# Transceivers.net
KiCad netlist of a schematic drawn in Altium Designer
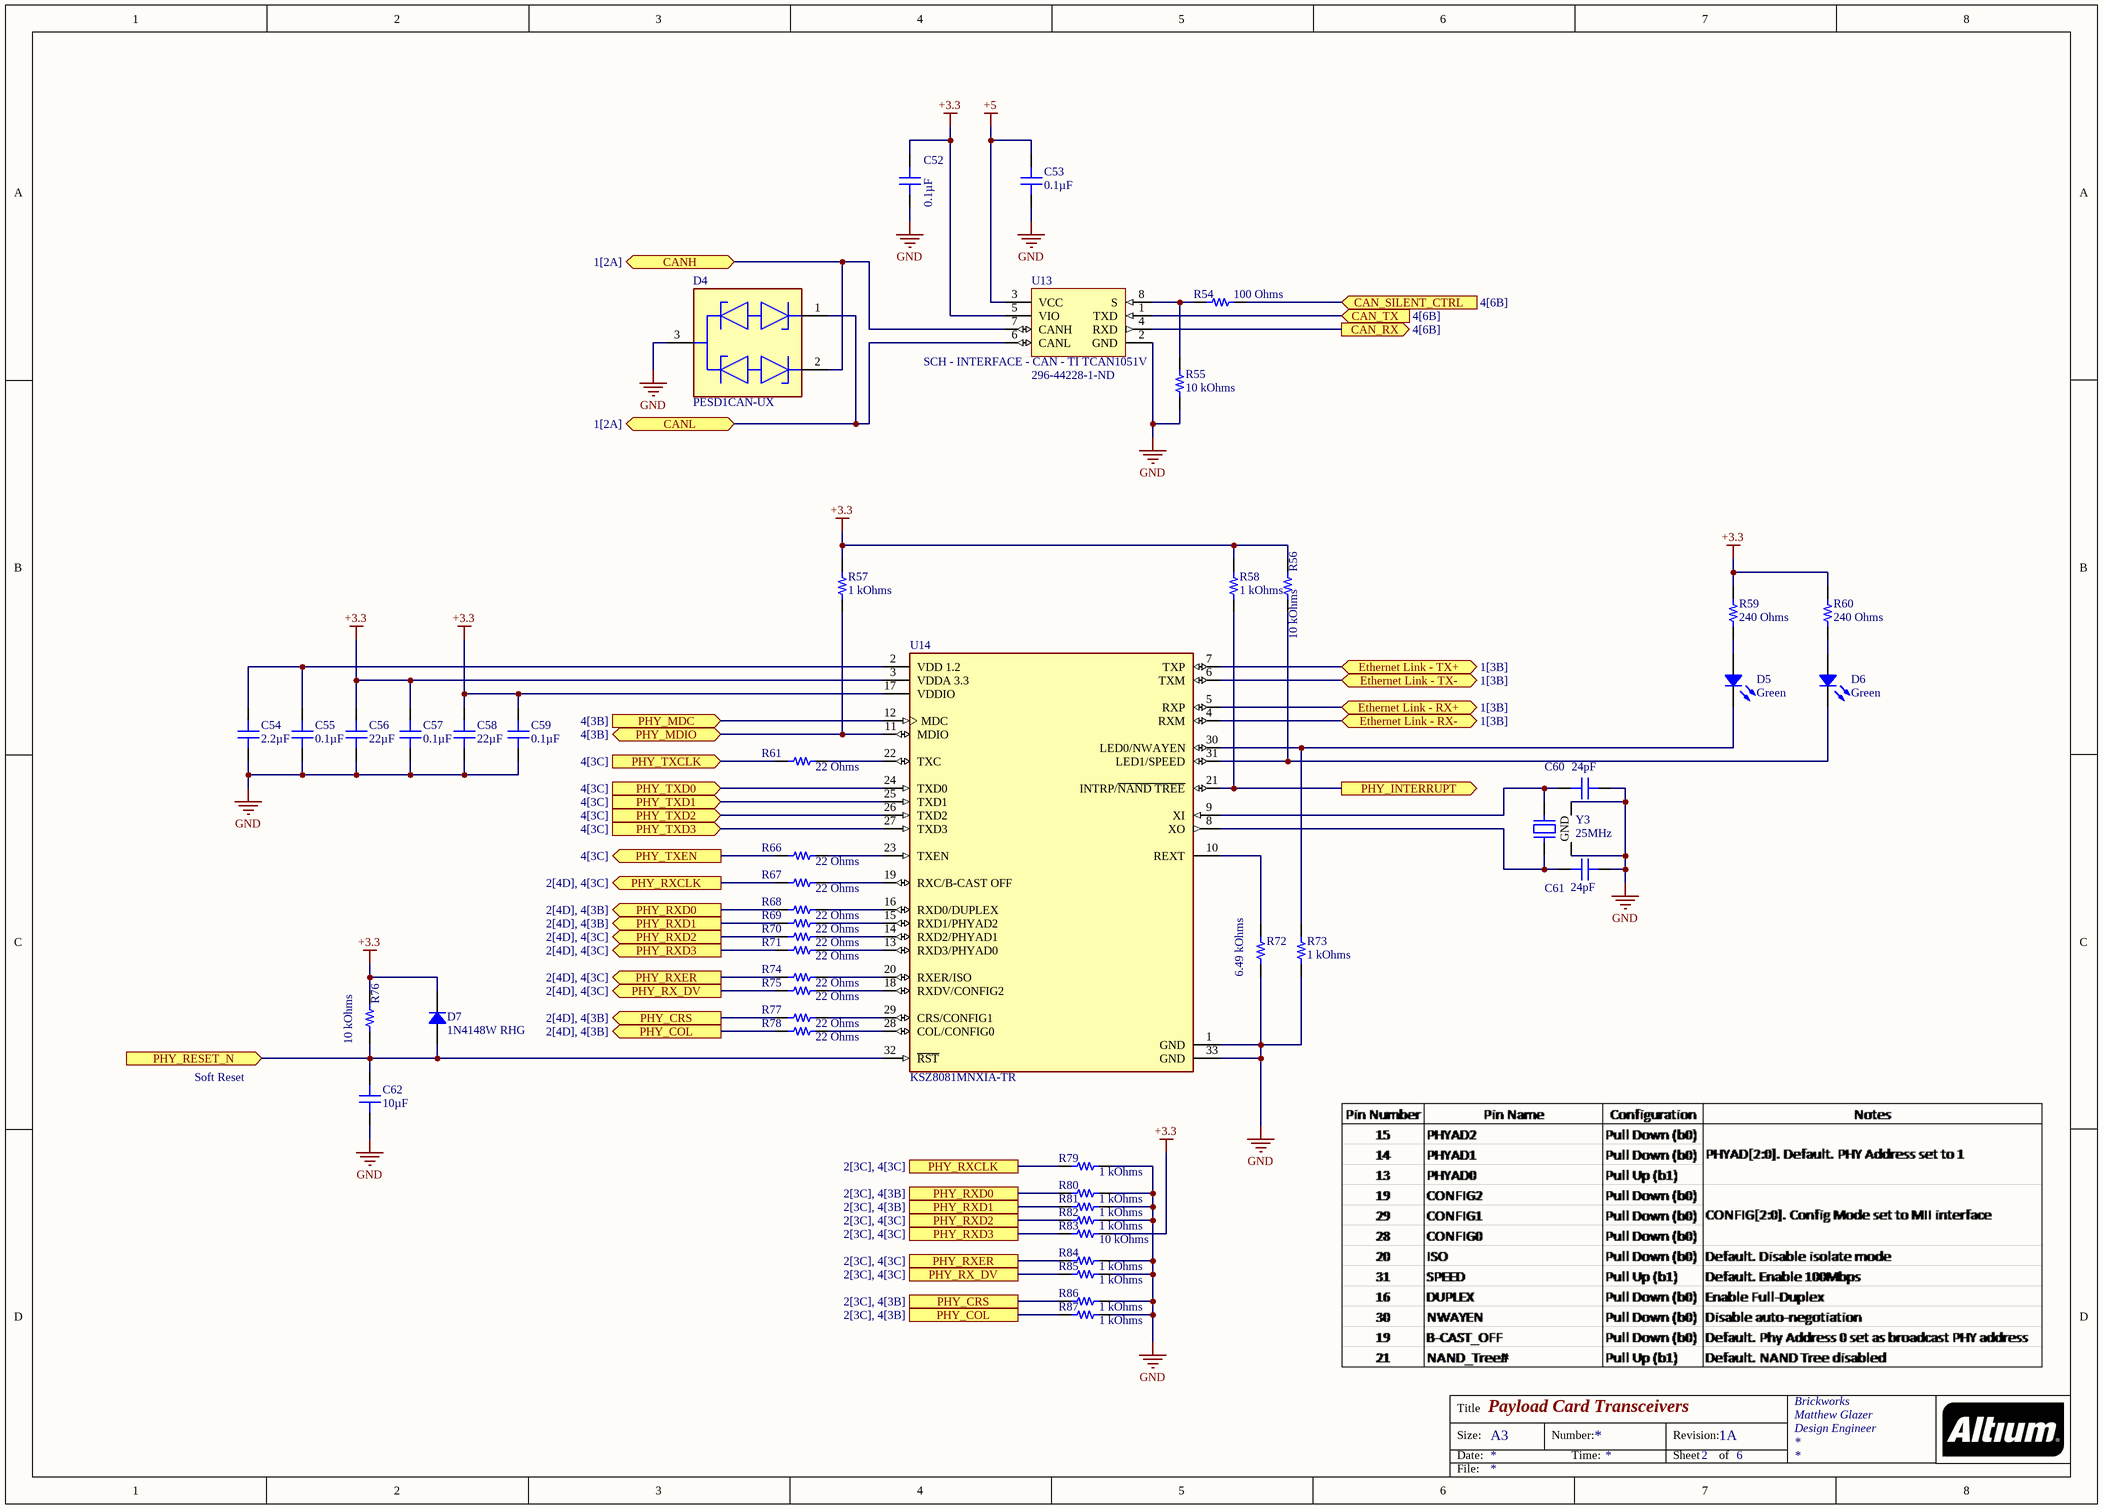
[diagram p0: Transceivers.SchDoc]

(export (version "E")
  (design (tool "Eeschema 10.0.6"))
  (components
    (comp (ref "C52")
      (value "0.1µF")
      (footprint "CAP 0603_1608")
      (description "CAP CER 0.1UF 25V X7R 0603")
      (fields
        (field (name "PART NUMBER") "CL10B104KA8WPNC")
        (field (name "MANUFACTURER") "Samsung Electro-Mechanics")
      )
      (libsource (lib "Celestial Altium Library - altium_library") (part "Capacitor"))
    )
    (comp (ref "C53")
      (value "0.1µF")
      (footprint "CAP 0603_1608")
      (description "CAP CER 0.1UF 25V X7R 0603")
      (fields
        (field (name "PART NUMBER") "CL10B104KA8WPNC")
        (field (name "MANUFACTURER") "Samsung Electro-Mechanics")
      )
      (libsource (lib "Celestial Altium Library - altium_library") (part "Capacitor"))
    )
    (comp (ref "C54")
      (value "2.2µF")
      (footprint "CAP 0805_2012")
      (description "CAP CER 2.2UF 10V X5R 0805")
      (fields
        (field (name "PART NUMBER") "CL21A225KPFNNNE")
        (field (name "MANUFACTURER") "Samsung Electro-Mechanics")
      )
      (libsource (lib "Celestial Altium Library - altium_library") (part "Capacitor"))
    )
    (comp (ref "C55")
      (value "0.1µF")
      (footprint "CAP 0603_1608")
      (description "CAP CER 0.1UF 25V X7R 0603")
      (fields
        (field (name "PART NUMBER") "CL10B104KA8WPNC")
        (field (name "MANUFACTURER") "Samsung Electro-Mechanics")
      )
      (libsource (lib "Celestial Altium Library - altium_library") (part "Capacitor"))
    )
    (comp (ref "C56")
      (value "22µF")
      (footprint "CAP 0805_2012")
      (description "CAP CER 22UF 10V X5R 0805")
      (fields
        (field (name "PART NUMBER") "CL21A226KPCLRNC")
        (field (name "MANUFACTURER") "Samsung Electro-Mechanics")
      )
      (libsource (lib "Celestial Altium Library - altium_library") (part "Capacitor"))
    )
    (comp (ref "C57")
      (value "0.1µF")
      (footprint "CAP 0603_1608")
      (description "CAP CER 0.1UF 25V X7R 0603")
      (fields
        (field (name "PART NUMBER") "CL10B104KA8WPNC")
        (field (name "MANUFACTURER") "Samsung Electro-Mechanics")
      )
      (libsource (lib "Celestial Altium Library - altium_library") (part "Capacitor"))
    )
    (comp (ref "C58")
      (value "22µF")
      (footprint "CAP 0805_2012")
      (description "CAP CER 22UF 10V X5R 0805")
      (fields
        (field (name "PART NUMBER") "CL21A226KPCLRNC")
        (field (name "MANUFACTURER") "Samsung Electro-Mechanics")
      )
      (libsource (lib "Celestial Altium Library - altium_library") (part "Capacitor"))
    )
    (comp (ref "C59")
      (value "0.1µF")
      (footprint "CAP 0603_1608")
      (description "CAP CER 0.1UF 25V X7R 0603")
      (fields
        (field (name "PART NUMBER") "CL10B104KA8WPNC")
        (field (name "MANUFACTURER") "Samsung Electro-Mechanics")
      )
      (libsource (lib "Celestial Altium Library - altium_library") (part "Capacitor"))
    )
    (comp (ref "C60")
      (value "24pF")
      (footprint "CAP 0603_1608")
      (description "CAP CER 24PF 50V C0G/NP0 0603")
      (fields
        (field (name "PART NUMBER") "CL10C240JB8NNNC")
        (field (name "MANUFACTURER") "Samsung Electro-Mechanics")
      )
      (libsource (lib "Celestial Altium Library - altium_library") (part "Capacitor"))
    )
    (comp (ref "C61")
      (value "24pF")
      (footprint "CAP 0603_1608")
      (description "CAP CER 24PF 50V C0G/NP0 0603")
      (fields
        (field (name "PART NUMBER") "CL10C240JB8NNNC")
        (field (name "MANUFACTURER") "Samsung Electro-Mechanics")
      )
      (libsource (lib "Celestial Altium Library - altium_library") (part "Capacitor"))
    )
    (comp (ref "C62")
      (value "10µF")
      (footprint "CAP 0805_2012")
      (description "CAP CER 10UF 16V X5R 0805")
      (fields (field (name "PART NUMBER") "CC0805KKX5R7BB106") (field (name "MANUFACTURER") "Yageo"))
      (libsource (lib "Celestial Altium Library - altium_library") (part "Capacitor"))
    )
    (comp (ref "D4")
      (value "PESD1CAN-UX")
      (footprint "FP-SOT323-MFG")
      (description "TVS DIODE 24V 50V SC70-3")
      (libsource (lib "Altium Content Vault") (part "04d57993b6b7b0f5b3c95ba4f97dea0"))
    )
    (comp (ref "D5")
      (value "Green")
      (footprint "LED 0603_1608 GREEN")
      (description "LED GREEN CLEAR CHIP SMD")
      (fields (field (name "PART NUMBER") "LTST-C193KGKT-5A") (field (name "MANUFACTURER") "Lite-On Inc."))
      (libsource (lib "Celestial Altium Library - altium_library") (part "LED"))
    )
    (comp (ref "D6")
      (value "Green")
      (footprint "LED 0603_1608 GREEN")
      (description "LED GREEN CLEAR CHIP SMD")
      (fields (field (name "PART NUMBER") "LTST-C193KGKT-5A") (field (name "MANUFACTURER") "Lite-On Inc."))
      (libsource (lib "Celestial Altium Library - altium_library") (part "LED"))
    )
    (comp (ref "D7")
      (value "1N4148W RHG")
      (footprint "SOD123F")
      (description "DIODE GEN PURP 100V 150MA SOD123")
      (fields (field (name "MANUFACTURER") "Taiwan Semiconductor Corporation"))
      (libsource (lib "Celestial Altium Library - altium_library") (part "Diode"))
    )
    (comp (ref "R54")
      (value "100 Ohms")
      (footprint "RES 0603_1608")
      (description "RES 100 OHM 1% 1/10W 0603")
      (fields
        (field (name "PART NUMBER") "RMCF0603FG100R")
        (field (name "MANUFACTURER") "Stackpole Electronics Inc")
      )
      (libsource (lib "Celestial Altium Library - altium_library") (part "Resistor"))
    )
    (comp (ref "R55")
      (value "10 kOhms")
      (footprint "RES 0603_1608")
      (description "RES 10K OHM 5% 1/10W 0603")
      (fields
        (field (name "PART NUMBER") "RMCF0603JT10K0")
        (field (name "MANUFACTURER") "Stackpole Electronics Inc")
      )
      (libsource (lib "Celestial Altium Library - altium_library") (part "Resistor"))
    )
    (comp (ref "R56")
      (value "10 kOhms")
      (footprint "RES 0603_1608")
      (description "RES 10K OHM 5% 1/10W 0603")
      (fields
        (field (name "PART NUMBER") "RMCF0603JT10K0")
        (field (name "MANUFACTURER") "Stackpole Electronics Inc")
      )
      (libsource (lib "Celestial Altium Library - altium_library") (part "Resistor"))
    )
    (comp (ref "R57")
      (value "1 kOhms")
      (footprint "RES 0603_1608")
      (description "RES 1K OHM 1% 1/8W 0603")
      (fields
        (field (name "PART NUMBER") "RNCP0603FTD1K00")
        (field (name "MANUFACTURER") "Stackpole Electronics Inc")
      )
      (libsource (lib "Celestial Altium Library - altium_library") (part "Resistor"))
    )
    (comp (ref "R58")
      (value "1 kOhms")
      (footprint "RES 0603_1608")
      (description "RES 1K OHM 1% 1/8W 0603")
      (fields
        (field (name "PART NUMBER") "RNCP0603FTD1K00")
        (field (name "MANUFACTURER") "Stackpole Electronics Inc")
      )
      (libsource (lib "Celestial Altium Library - altium_library") (part "Resistor"))
    )
    (comp (ref "R59")
      (value "240 Ohms")
      (footprint "RES 0603_1608")
      (description "RES 240 OHM 5% 1/10W 0603")
      (fields
        (field (name "PART NUMBER") "RMCF0603JT240R")
        (field (name "MANUFACTURER") "Stackpole Electronics Inc")
      )
      (libsource (lib "Celestial Altium Library - altium_library") (part "Resistor"))
    )
    (comp (ref "R60")
      (value "240 Ohms")
      (footprint "RES 0603_1608")
      (description "RES 240 OHM 5% 1/10W 0603")
      (fields
        (field (name "PART NUMBER") "RMCF0603JT240R")
        (field (name "MANUFACTURER") "Stackpole Electronics Inc")
      )
      (libsource (lib "Celestial Altium Library - altium_library") (part "Resistor"))
    )
    (comp (ref "R61")
      (value "22 Ohms")
      (footprint "RES 0603_1608")
      (description "RES 22 OHM 1% 1/10W 0603")
      (fields
        (field (name "PART NUMBER") "RMCF0603FT22R0")
        (field (name "MANUFACTURER") "Stackpole Electronics Inc")
      )
      (libsource (lib "Celestial Altium Library - altium_library") (part "Resistor"))
    )
    (comp (ref "R66")
      (value "22 Ohms")
      (footprint "RES 0603_1608")
      (description "RES 22 OHM 1% 1/10W 0603")
      (fields
        (field (name "PART NUMBER") "RMCF0603FT22R0")
        (field (name "MANUFACTURER") "Stackpole Electronics Inc")
      )
      (libsource (lib "Celestial Altium Library - altium_library") (part "Resistor"))
    )
    (comp (ref "R67")
      (value "22 Ohms")
      (footprint "RES 0603_1608")
      (description "RES 22 OHM 1% 1/10W 0603")
      (fields
        (field (name "PART NUMBER") "RMCF0603FT22R0")
        (field (name "MANUFACTURER") "Stackpole Electronics Inc")
      )
      (libsource (lib "Celestial Altium Library - altium_library") (part "Resistor"))
    )
    (comp (ref "R68")
      (value "22 Ohms")
      (footprint "RES 0603_1608")
      (description "RES 22 OHM 1% 1/10W 0603")
      (fields
        (field (name "PART NUMBER") "RMCF0603FT22R0")
        (field (name "MANUFACTURER") "Stackpole Electronics Inc")
      )
      (libsource (lib "Celestial Altium Library - altium_library") (part "Resistor"))
    )
    (comp (ref "R69")
      (value "22 Ohms")
      (footprint "RES 0603_1608")
      (description "RES 22 OHM 1% 1/10W 0603")
      (fields
        (field (name "PART NUMBER") "RMCF0603FT22R0")
        (field (name "MANUFACTURER") "Stackpole Electronics Inc")
      )
      (libsource (lib "Celestial Altium Library - altium_library") (part "Resistor"))
    )
    (comp (ref "R70")
      (value "22 Ohms")
      (footprint "RES 0603_1608")
      (description "RES 22 OHM 1% 1/10W 0603")
      (fields
        (field (name "PART NUMBER") "RMCF0603FT22R0")
        (field (name "MANUFACTURER") "Stackpole Electronics Inc")
      )
      (libsource (lib "Celestial Altium Library - altium_library") (part "Resistor"))
    )
    (comp (ref "R71")
      (value "22 Ohms")
      (footprint "RES 0603_1608")
      (description "RES 22 OHM 1% 1/10W 0603")
      (fields
        (field (name "PART NUMBER") "RMCF0603FT22R0")
        (field (name "MANUFACTURER") "Stackpole Electronics Inc")
      )
      (libsource (lib "Celestial Altium Library - altium_library") (part "Resistor"))
    )
    (comp (ref "R72")
      (value "6.49 kOhms")
      (footprint "RES 0603_1608")
      (description "RES 6.49K OHM 1% 1/8W 0603")
      (fields
        (field (name "PART NUMBER") "RNCP0603FTD6K49")
        (field (name "MANUFACTURER") "Stackpole Electronics Inc")
      )
      (libsource (lib "Celestial Altium Library - altium_library") (part "Resistor"))
    )
    (comp (ref "R73")
      (value "1 kOhms")
      (footprint "RES 0603_1608")
      (description "RES 1K OHM 1% 1/8W 0603")
      (fields
        (field (name "PART NUMBER") "RNCP0603FTD1K00")
        (field (name "MANUFACTURER") "Stackpole Electronics Inc")
      )
      (libsource (lib "Celestial Altium Library - altium_library") (part "Resistor"))
    )
    (comp (ref "R74")
      (value "22 Ohms")
      (footprint "RES 0603_1608")
      (description "RES 22 OHM 1% 1/10W 0603")
      (fields
        (field (name "PART NUMBER") "RMCF0603FT22R0")
        (field (name "MANUFACTURER") "Stackpole Electronics Inc")
      )
      (libsource (lib "Celestial Altium Library - altium_library") (part "Resistor"))
    )
    (comp (ref "R75")
      (value "22 Ohms")
      (footprint "RES 0603_1608")
      (description "RES 22 OHM 1% 1/10W 0603")
      (fields
        (field (name "PART NUMBER") "RMCF0603FT22R0")
        (field (name "MANUFACTURER") "Stackpole Electronics Inc")
      )
      (libsource (lib "Celestial Altium Library - altium_library") (part "Resistor"))
    )
    (comp (ref "R76")
      (value "10 kOhms")
      (footprint "RES 0603_1608")
      (description "RES 10K OHM 5% 1/10W 0603")
      (fields
        (field (name "PART NUMBER") "RMCF0603JT10K0")
        (field (name "MANUFACTURER") "Stackpole Electronics Inc")
      )
      (libsource (lib "Celestial Altium Library - altium_library") (part "Resistor"))
    )
    (comp (ref "R77")
      (value "22 Ohms")
      (footprint "RES 0603_1608")
      (description "RES 22 OHM 1% 1/10W 0603")
      (fields
        (field (name "PART NUMBER") "RMCF0603FT22R0")
        (field (name "MANUFACTURER") "Stackpole Electronics Inc")
      )
      (libsource (lib "Celestial Altium Library - altium_library") (part "Resistor"))
    )
    (comp (ref "R78")
      (value "22 Ohms")
      (footprint "RES 0603_1608")
      (description "RES 22 OHM 1% 1/10W 0603")
      (fields
        (field (name "PART NUMBER") "RMCF0603FT22R0")
        (field (name "MANUFACTURER") "Stackpole Electronics Inc")
      )
      (libsource (lib "Celestial Altium Library - altium_library") (part "Resistor"))
    )
    (comp (ref "R79")
      (value "1 kOhms")
      (footprint "RES 0603_1608")
      (description "RES 1K OHM 1% 1/8W 0603")
      (fields
        (field (name "PART NUMBER") "RNCP0603FTD1K00")
        (field (name "MANUFACTURER") "Stackpole Electronics Inc")
      )
      (libsource (lib "Celestial Altium Library - altium_library") (part "Resistor"))
    )
    (comp (ref "R80")
      (value "1 kOhms")
      (footprint "RES 0603_1608")
      (description "RES 1K OHM 1% 1/8W 0603")
      (fields
        (field (name "PART NUMBER") "RNCP0603FTD1K00")
        (field (name "MANUFACTURER") "Stackpole Electronics Inc")
      )
      (libsource (lib "Celestial Altium Library - altium_library") (part "Resistor"))
    )
    (comp (ref "R81")
      (value "1 kOhms")
      (footprint "RES 0603_1608")
      (description "RES 1K OHM 1% 1/8W 0603")
      (fields
        (field (name "PART NUMBER") "RNCP0603FTD1K00")
        (field (name "MANUFACTURER") "Stackpole Electronics Inc")
      )
      (libsource (lib "Celestial Altium Library - altium_library") (part "Resistor"))
    )
    (comp (ref "R82")
      (value "1 kOhms")
      (footprint "RES 0603_1608")
      (description "RES 1K OHM 1% 1/8W 0603")
      (fields
        (field (name "PART NUMBER") "RNCP0603FTD1K00")
        (field (name "MANUFACTURER") "Stackpole Electronics Inc")
      )
      (libsource (lib "Celestial Altium Library - altium_library") (part "Resistor"))
    )
    (comp (ref "R83")
      (value "10 kOhms")
      (footprint "RES 0603_1608")
      (description "RES 10K OHM 5% 1/10W 0603")
      (fields
        (field (name "PART NUMBER") "RMCF0603JT10K0")
        (field (name "MANUFACTURER") "Stackpole Electronics Inc")
      )
      (libsource (lib "Celestial Altium Library - altium_library") (part "Resistor"))
    )
    (comp (ref "R84")
      (value "1 kOhms")
      (footprint "RES 0603_1608")
      (description "RES 1K OHM 1% 1/8W 0603")
      (fields
        (field (name "PART NUMBER") "RNCP0603FTD1K00")
        (field (name "MANUFACTURER") "Stackpole Electronics Inc")
      )
      (libsource (lib "Celestial Altium Library - altium_library") (part "Resistor"))
    )
    (comp (ref "R85")
      (value "1 kOhms")
      (footprint "RES 0603_1608")
      (description "RES 1K OHM 1% 1/8W 0603")
      (fields
        (field (name "PART NUMBER") "RNCP0603FTD1K00")
        (field (name "MANUFACTURER") "Stackpole Electronics Inc")
      )
      (libsource (lib "Celestial Altium Library - altium_library") (part "Resistor"))
    )
    (comp (ref "R86")
      (value "1 kOhms")
      (footprint "RES 0603_1608")
      (description "RES 1K OHM 1% 1/8W 0603")
      (fields
        (field (name "PART NUMBER") "RNCP0603FTD1K00")
        (field (name "MANUFACTURER") "Stackpole Electronics Inc")
      )
      (libsource (lib "Celestial Altium Library - altium_library") (part "Resistor"))
    )
    (comp (ref "R87")
      (value "1 kOhms")
      (footprint "RES 0603_1608")
      (description "RES 1K OHM 1% 1/8W 0603")
      (fields
        (field (name "PART NUMBER") "RNCP0603FTD1K00")
        (field (name "MANUFACTURER") "Stackpole Electronics Inc")
      )
      (libsource (lib "Celestial Altium Library - altium_library") (part "Resistor"))
    )
    (comp (ref "U13")
      (value "SCH - INTERFACE - CAN - TI TCAN1051V")
      (footprint "PCB - LEADS - SOIC - TI SOIC-8")
      (fields (field (name "SUPPLIER PART NUMBER 1") "296-44228-1-ND"))
      (libsource (lib "HAB_ICs") (part "SCH - INTERFACE - CAN - TI TCAN1051V"))
    )
    (comp (ref "U14")
      (value "KSZ8081MNXIA-TR")
      (footprint "FP-QFN55-32LD-PL-5-MFG")
      (description "IC TRANSCEIVER FULL 1/1 32QFN")
      (fields
        (field (name "OCTOPART") "https://octopart.com/ksz8081mnxia-tr-microchip-66799958")
        (field (name "MANUFACTURER") "Microchip")
      )
      (libsource (lib "Altium Content Vault") (part "882547a6550c82911a23300368c51e3"))
    )
    (comp (ref "Y3")
      (value "25MHz")
      (footprint "EPSON TSX-3225")
      (description "CRYSTAL 25.0000MHZ 18PF SMD")
      (fields (field (name "PART NUMBER") "TSX-3225 25.0000MF20P-C0") (field (name "MANUFACTURER") "EPSON"))
      (libsource (lib "Celestial Altium Library - altium_library") (part "Epson Crystal TSX-3225"))
    )
  )
  (nets
    (net (code "1") (name "+3.3") (class "Default")
      (node (ref "C52") (pin "2") (pinfunction "2_2") (pintype "passive"))
      (node (ref "C56") (pin "2") (pinfunction "2_2") (pintype "passive"))
      (node (ref "C57") (pin "2") (pinfunction "2_2") (pintype "passive"))
      (node (ref "C58") (pin "2") (pinfunction "2_2") (pintype "passive"))
      (node (ref "C59") (pin "2") (pinfunction "2_2") (pintype "passive"))
      (node (ref "D7") (pin "2") (pinfunction "2_2") (pintype "passive"))
      (node (ref "R56") (pin "2") (pinfunction "2_2") (pintype "passive"))
      (node (ref "R57") (pin "2") (pinfunction "2_2") (pintype "passive"))
      (node (ref "R58") (pin "2") (pinfunction "2_2") (pintype "passive"))
      (node (ref "R59") (pin "2") (pinfunction "2_2") (pintype "passive"))
      (node (ref "R60") (pin "2") (pinfunction "2_2") (pintype "passive"))
      (node (ref "R76") (pin "2") (pinfunction "2_2") (pintype "passive"))
      (node (ref "R83") (pin "1") (pinfunction "1_1") (pintype "passive"))
      (node (ref "U13") (pin "5") (pinfunction "VIO_5") (pintype "power_in"))
      (node (ref "U14") (pin "17") (pinfunction "VDDIO_17") (pintype "power_in"))
      (node (ref "U14") (pin "3") (pinfunction "VDDA_3.3_3") (pintype "power_in"))
    )
    (net (code "2") (name "+5") (class "Default")
      (node (ref "C53") (pin "2") (pinfunction "2_2") (pintype "passive"))
      (node (ref "U13") (pin "3") (pinfunction "VCC_3") (pintype "power_in"))
    )
    (net (code "3") (name "/CANH") (class "Default")
      (node (ref "D4") (pin "2") (pinfunction "cathode_2_2") (pintype "passive"))
      (node (ref "U13") (pin "7") (pinfunction "CANH_7") (pintype "bidirectional"))
    )
    (net (code "4") (name "/CANL") (class "Default")
      (node (ref "D4") (pin "1") (pinfunction "cathode_1_1") (pintype "passive"))
      (node (ref "U13") (pin "6") (pinfunction "CANL_6") (pintype "bidirectional"))
    )
    (net (code "5") (name "/CAN_RX") (class "Default")
      (node (ref "U13") (pin "4") (pinfunction "RXD_4") (pintype "output"))
    )
    (net (code "6") (name "/CAN_SILENT_CTRL") (class "Default")
      (node (ref "R54") (pin "2") (pinfunction "2_2") (pintype "passive"))
    )
    (net (code "7") (name "/CAN_TX") (class "Default")
      (node (ref "U13") (pin "1") (pinfunction "TXD_1") (pintype "input"))
    )
    (net (code "8") (name "/Ethernet Link - RX+") (class "Default")
      (node (ref "U14") (pin "5") (pinfunction "RXP_5") (pintype "bidirectional"))
    )
    (net (code "9") (name "/Ethernet Link - RX-") (class "Default")
      (node (ref "U14") (pin "4") (pinfunction "RXM_4") (pintype "bidirectional"))
    )
    (net (code "10") (name "/Ethernet Link - TX+") (class "Default")
      (node (ref "U14") (pin "7") (pinfunction "TXP_7") (pintype "bidirectional"))
    )
    (net (code "11") (name "/Ethernet Link - TX-") (class "Default")
      (node (ref "U14") (pin "6") (pinfunction "TXM_6") (pintype "bidirectional"))
    )
    (net (code "12") (name "/PHY_COL") (class "Default")
      (node (ref "R78") (pin "1") (pinfunction "1_1") (pintype "passive"))
      (node (ref "R87") (pin "2") (pinfunction "2_2") (pintype "passive"))
    )
    (net (code "13") (name "/PHY_CRS") (class "Default")
      (node (ref "R77") (pin "1") (pinfunction "1_1") (pintype "passive"))
      (node (ref "R86") (pin "2") (pinfunction "2_2") (pintype "passive"))
    )
    (net (code "14") (name "/PHY_INTERRUPT") (class "Default")
      (node (ref "R58") (pin "1") (pinfunction "1_1") (pintype "passive"))
      (node (ref "U14") (pin "21") (pinfunction "INTRP/~{NAND_TREE}_21") (pintype "bidirectional"))
    )
    (net (code "15") (name "/PHY_MDC") (class "Default")
      (node (ref "U14") (pin "12") (pinfunction "MDC_12") (pintype "input"))
    )
    (net (code "16") (name "/PHY_MDIO") (class "Default")
      (node (ref "R57") (pin "1") (pinfunction "1_1") (pintype "passive"))
      (node (ref "U14") (pin "11") (pinfunction "MDIO_11") (pintype "bidirectional"))
    )
    (net (code "17") (name "/PHY_RESET_N") (class "Default")
      (node (ref "C62") (pin "2") (pinfunction "2_2") (pintype "passive"))
      (node (ref "D7") (pin "1") (pinfunction "1_1") (pintype "passive"))
      (node (ref "R76") (pin "1") (pinfunction "1_1") (pintype "passive"))
      (node (ref "U14") (pin "32") (pinfunction "~{RST}_32") (pintype "input"))
    )
    (net (code "18") (name "/PHY_RXCLK") (class "Default")
      (node (ref "R67") (pin "1") (pinfunction "1_1") (pintype "passive"))
      (node (ref "R79") (pin "2") (pinfunction "2_2") (pintype "passive"))
    )
    (net (code "19") (name "/PHY_RXD0") (class "Default")
      (node (ref "R68") (pin "1") (pinfunction "1_1") (pintype "passive"))
      (node (ref "R80") (pin "2") (pinfunction "2_2") (pintype "passive"))
    )
    (net (code "20") (name "/PHY_RXD1") (class "Default")
      (node (ref "R69") (pin "1") (pinfunction "1_1") (pintype "passive"))
      (node (ref "R81") (pin "2") (pinfunction "2_2") (pintype "passive"))
    )
    (net (code "21") (name "/PHY_RXD2") (class "Default")
      (node (ref "R70") (pin "1") (pinfunction "1_1") (pintype "passive"))
      (node (ref "R82") (pin "2") (pinfunction "2_2") (pintype "passive"))
    )
    (net (code "22") (name "/PHY_RXD3") (class "Default")
      (node (ref "R71") (pin "1") (pinfunction "1_1") (pintype "passive"))
      (node (ref "R83") (pin "2") (pinfunction "2_2") (pintype "passive"))
    )
    (net (code "23") (name "/PHY_RXER") (class "Default")
      (node (ref "R74") (pin "1") (pinfunction "1_1") (pintype "passive"))
      (node (ref "R84") (pin "2") (pinfunction "2_2") (pintype "passive"))
    )
    (net (code "24") (name "/PHY_RX_DV") (class "Default")
      (node (ref "R75") (pin "1") (pinfunction "1_1") (pintype "passive"))
      (node (ref "R85") (pin "2") (pinfunction "2_2") (pintype "passive"))
    )
    (net (code "25") (name "/PHY_TXCLK") (class "Default")
      (node (ref "R61") (pin "1") (pinfunction "1_1") (pintype "passive"))
    )
    (net (code "26") (name "/PHY_TXD0") (class "Default")
      (node (ref "U14") (pin "24") (pinfunction "TXD0_24") (pintype "input"))
    )
    (net (code "27") (name "/PHY_TXD1") (class "Default")
      (node (ref "U14") (pin "25") (pinfunction "TXD1_25") (pintype "input"))
    )
    (net (code "28") (name "/PHY_TXD2") (class "Default")
      (node (ref "U14") (pin "26") (pinfunction "TXD2_26") (pintype "input"))
    )
    (net (code "29") (name "/PHY_TXD3") (class "Default")
      (node (ref "U14") (pin "27") (pinfunction "TXD3_27") (pintype "input"))
    )
    (net (code "30") (name "/PHY_TXEN") (class "Default")
      (node (ref "R66") (pin "1") (pinfunction "1_1") (pintype "passive"))
    )
    (net (code "31") (name "GND") (class "Default")
      (node (ref "C52") (pin "1") (pinfunction "1_1") (pintype "passive"))
      (node (ref "C53") (pin "1") (pinfunction "1_1") (pintype "passive"))
      (node (ref "C54") (pin "1") (pinfunction "1_1") (pintype "passive"))
      (node (ref "C55") (pin "1") (pinfunction "1_1") (pintype "passive"))
      (node (ref "C56") (pin "1") (pinfunction "1_1") (pintype "passive"))
      (node (ref "C57") (pin "1") (pinfunction "1_1") (pintype "passive"))
      (node (ref "C58") (pin "1") (pinfunction "1_1") (pintype "passive"))
      (node (ref "C59") (pin "1") (pinfunction "1_1") (pintype "passive"))
      (node (ref "C60") (pin "2") (pinfunction "2_2") (pintype "passive"))
      (node (ref "C61") (pin "2") (pinfunction "2_2") (pintype "passive"))
      (node (ref "C62") (pin "1") (pinfunction "1_1") (pintype "passive"))
      (node (ref "D4") (pin "3") (pinfunction "common_cathode_3") (pintype "passive"))
      (node (ref "R55") (pin "1") (pinfunction "1_1") (pintype "passive"))
      (node (ref "R72") (pin "1") (pinfunction "1_1") (pintype "passive"))
      (node (ref "R73") (pin "1") (pinfunction "1_1") (pintype "passive"))
      (node (ref "R79") (pin "1") (pinfunction "1_1") (pintype "passive"))
      (node (ref "R80") (pin "1") (pinfunction "1_1") (pintype "passive"))
      (node (ref "R81") (pin "1") (pinfunction "1_1") (pintype "passive"))
      (node (ref "R82") (pin "1") (pinfunction "1_1") (pintype "passive"))
      (node (ref "R84") (pin "1") (pinfunction "1_1") (pintype "passive"))
      (node (ref "R85") (pin "1") (pinfunction "1_1") (pintype "passive"))
      (node (ref "R86") (pin "1") (pinfunction "1_1") (pintype "passive"))
      (node (ref "R87") (pin "1") (pinfunction "1_1") (pintype "passive"))
      (node (ref "U13") (pin "2") (pinfunction "GND_2") (pintype "power_in"))
      (node (ref "U14") (pin "1") (pinfunction "GND_1") (pintype "power_in"))
      (node (ref "U14") (pin "33") (pinfunction "GND_33") (pintype "power_in"))
      (node (ref "Y3") (pin "2") (pinfunction "GND_2") (pintype "passive"))
      (node (ref "Y3") (pin "4") (pinfunction "GND_4") (pintype "passive"))
    )
    (net (code "32") (name "Net-(D5-Pad1)") (class "Default")
      (node (ref "D5") (pin "1") (pinfunction "1_1") (pintype "passive"))
      (node (ref "R59") (pin "1") (pinfunction "1_1") (pintype "passive"))
    )
    (net (code "33") (name "Net-(D6-Pad1)") (class "Default")
      (node (ref "D6") (pin "1") (pinfunction "1_1") (pintype "passive"))
      (node (ref "R60") (pin "1") (pinfunction "1_1") (pintype "passive"))
    )
    (net (code "34") (name "Net-(U13-S)") (class "Default")
      (node (ref "R54") (pin "1") (pinfunction "1_1") (pintype "passive"))
      (node (ref "R55") (pin "2") (pinfunction "2_2") (pintype "passive"))
      (node (ref "U13") (pin "8") (pinfunction "S_8") (pintype "input"))
    )
    (net (code "35") (name "Net-(U14-COL{slash}CONFIG0)") (class "Default")
      (node (ref "R78") (pin "2") (pinfunction "2_2") (pintype "passive"))
      (node (ref "U14") (pin "28") (pinfunction "COL/CONFIG0_28") (pintype "bidirectional"))
    )
    (net (code "36") (name "Net-(U14-CRS{slash}CONFIG1)") (class "Default")
      (node (ref "R77") (pin "2") (pinfunction "2_2") (pintype "passive"))
      (node (ref "U14") (pin "29") (pinfunction "CRS/CONFIG1_29") (pintype "bidirectional"))
    )
    (net (code "37") (name "Net-(U14-LED0{slash}NWAYEN)") (class "Default")
      (node (ref "D5") (pin "2") (pinfunction "2_2") (pintype "passive"))
      (node (ref "R73") (pin "2") (pinfunction "2_2") (pintype "passive"))
      (node (ref "U14") (pin "30") (pinfunction "LED0/NWAYEN_30") (pintype "bidirectional"))
    )
    (net (code "38") (name "Net-(U14-LED1{slash}SPEED)") (class "Default")
      (node (ref "D6") (pin "2") (pinfunction "2_2") (pintype "passive"))
      (node (ref "R56") (pin "1") (pinfunction "1_1") (pintype "passive"))
      (node (ref "U14") (pin "31") (pinfunction "LED1/SPEED_31") (pintype "bidirectional"))
    )
    (net (code "39") (name "Net-(U14-REXT)") (class "Default")
      (node (ref "R72") (pin "2") (pinfunction "2_2") (pintype "passive"))
      (node (ref "U14") (pin "10") (pinfunction "REXT_10") (pintype "passive"))
    )
    (net (code "40") (name "Net-(U14-RXC{slash}B-CAST_OFF)") (class "Default")
      (node (ref "R67") (pin "2") (pinfunction "2_2") (pintype "passive"))
      (node (ref "U14") (pin "19") (pinfunction "RXC/B-CAST_OFF_19") (pintype "bidirectional"))
    )
    (net (code "41") (name "Net-(U14-RXD0{slash}DUPLEX)") (class "Default")
      (node (ref "R68") (pin "2") (pinfunction "2_2") (pintype "passive"))
      (node (ref "U14") (pin "16") (pinfunction "RXD0/DUPLEX_16") (pintype "bidirectional"))
    )
    (net (code "42") (name "Net-(U14-RXD1{slash}PHYAD2)") (class "Default")
      (node (ref "R69") (pin "2") (pinfunction "2_2") (pintype "passive"))
      (node (ref "U14") (pin "15") (pinfunction "RXD1/PHYAD2_15") (pintype "bidirectional"))
    )
    (net (code "43") (name "Net-(U14-RXD2{slash}PHYAD1)") (class "Default")
      (node (ref "R70") (pin "2") (pinfunction "2_2") (pintype "passive"))
      (node (ref "U14") (pin "14") (pinfunction "RXD2/PHYAD1_14") (pintype "bidirectional"))
    )
    (net (code "44") (name "Net-(U14-RXD3{slash}PHYAD0)") (class "Default")
      (node (ref "R71") (pin "2") (pinfunction "2_2") (pintype "passive"))
      (node (ref "U14") (pin "13") (pinfunction "RXD3/PHYAD0_13") (pintype "bidirectional"))
    )
    (net (code "45") (name "Net-(U14-RXDV{slash}CONFIG2)") (class "Default")
      (node (ref "R75") (pin "2") (pinfunction "2_2") (pintype "passive"))
      (node (ref "U14") (pin "18") (pinfunction "RXDV/CONFIG2_18") (pintype "bidirectional"))
    )
    (net (code "46") (name "Net-(U14-RXER{slash}ISO)") (class "Default")
      (node (ref "R74") (pin "2") (pinfunction "2_2") (pintype "passive"))
      (node (ref "U14") (pin "20") (pinfunction "RXER/ISO_20") (pintype "bidirectional"))
    )
    (net (code "47") (name "Net-(U14-TXC)") (class "Default")
      (node (ref "R61") (pin "2") (pinfunction "2_2") (pintype "passive"))
      (node (ref "U14") (pin "22") (pinfunction "TXC_22") (pintype "bidirectional"))
    )
    (net (code "48") (name "Net-(U14-TXEN)") (class "Default")
      (node (ref "R66") (pin "2") (pinfunction "2_2") (pintype "passive"))
      (node (ref "U14") (pin "23") (pinfunction "TXEN_23") (pintype "input"))
    )
    (net (code "49") (name "Net-(U14-VDD_1.2)") (class "Default")
      (node (ref "C54") (pin "2") (pinfunction "2_2") (pintype "passive"))
      (node (ref "C55") (pin "2") (pinfunction "2_2") (pintype "passive"))
      (node (ref "U14") (pin "2") (pinfunction "VDD_1.2_2") (pintype "power_in"))
    )
    (net (code "50") (name "Net-(U14-XI)") (class "Default")
      (node (ref "C60") (pin "1") (pinfunction "1_1") (pintype "passive"))
      (node (ref "U14") (pin "9") (pinfunction "XI_9") (pintype "input"))
      (node (ref "Y3") (pin "3") (pinfunction "3_3") (pintype "passive"))
    )
    (net (code "51") (name "Net-(U14-XO)") (class "Default")
      (node (ref "C61") (pin "1") (pinfunction "1_1") (pintype "passive"))
      (node (ref "U14") (pin "8") (pinfunction "XO_8") (pintype "output"))
      (node (ref "Y3") (pin "1") (pinfunction "1_1") (pintype "passive"))
    )
  )
)
